# FootVibrator.net
KiCad netlist of a schematic drawn in EAGLE
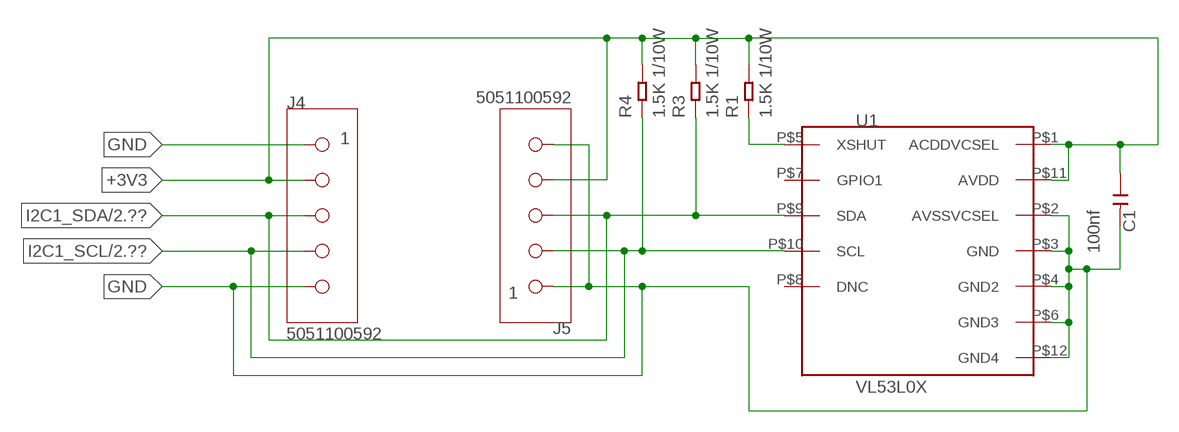
[diagram p0: schematic, sheet 1]
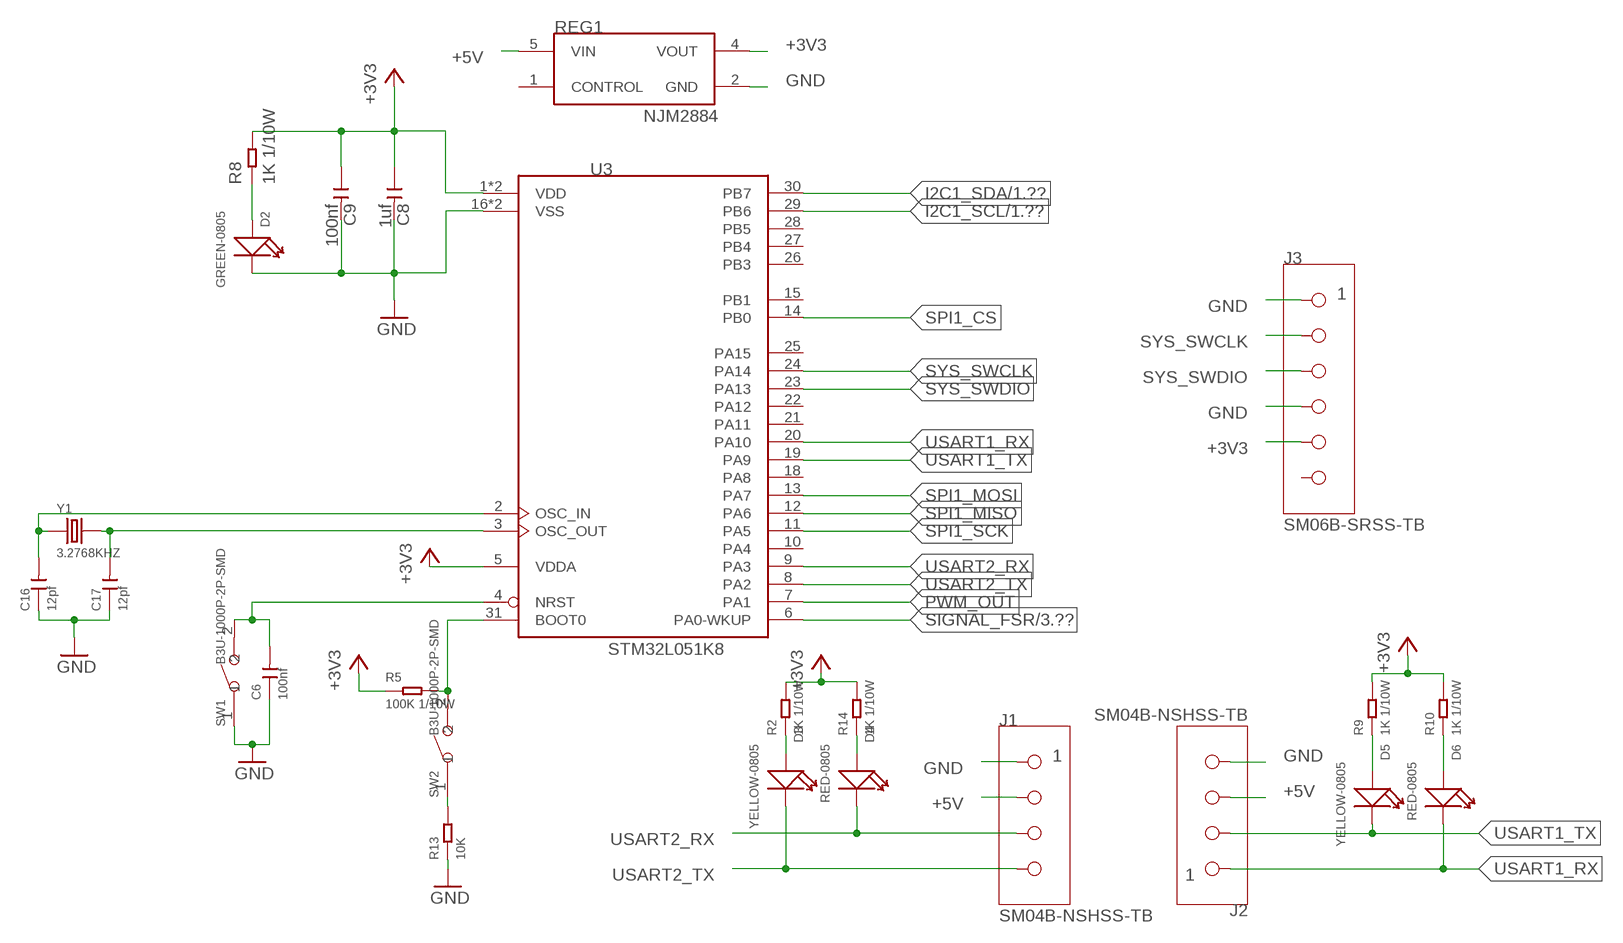
[diagram p1: schematic, sheet 2]
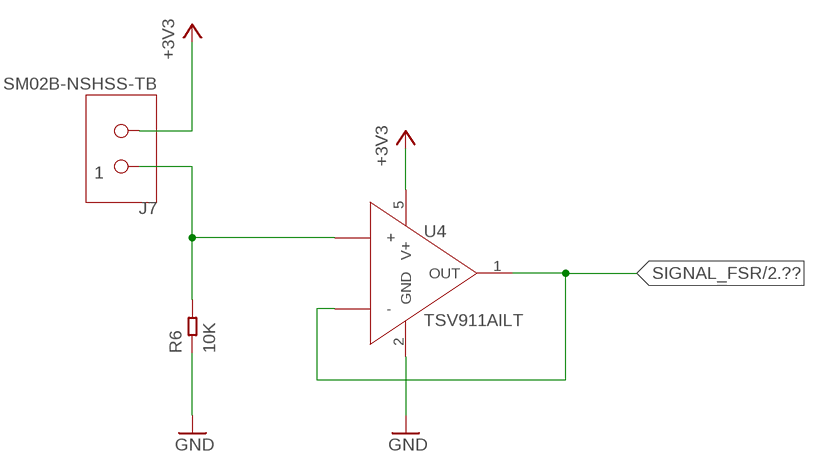
[diagram p2: schematic, sheet 3]
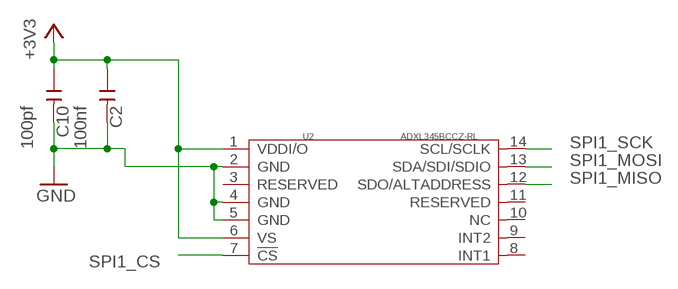
[diagram p3: schematic, sheet 4]
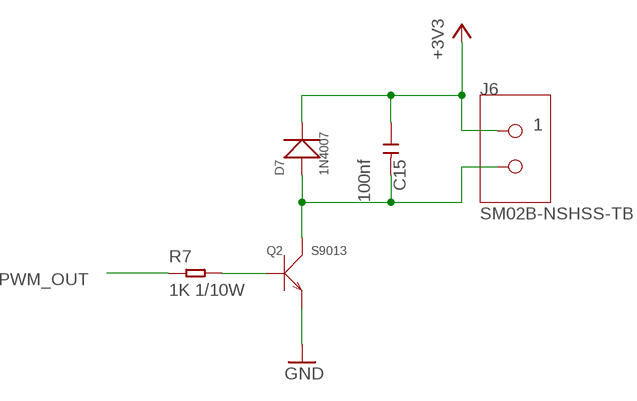
[diagram p4: schematic, sheet 5]

(export (version "E")
  (design (tool "Eeschema 10.0.6"))
  (components
    (comp (ref "C6")
      (value "100nf")
      (footprint "eagle-import:C0603")
      (fields (field (name "MPN") "CC0603KRX7R9BB104"))
      (libsource (lib "eagle-import") (part "CERAMIC-100NF-50V-10%-X7R(0603)"))
    )
    (comp (ref "C8")
      (value "1uf")
      (footprint "eagle-import:C0603")
      (fields (field (name "MPN") "CC0603KRX7R8BB105"))
      (libsource (lib "eagle-import") (part "CERAMIC-1UF-25V-10%-X7R(0603)"))
    )
    (comp (ref "C9")
      (value "100nf")
      (footprint "eagle-import:C0603")
      (fields (field (name "MPN") "CC0603KRX7R9BB104"))
      (libsource (lib "eagle-import") (part "CERAMIC-100NF-50V-10%-X7R(0603)"))
    )
    (comp (ref "C16")
      (value "12pf")
      (footprint "eagle-import:C0603")
      (fields (field (name "MPN") "CC0603JRNPO9BN120"))
      (libsource (lib "eagle-import") (part "CERAMIC-12PF-50V-5%-NPO(0603)"))
    )
    (comp (ref "C17")
      (value "12pf")
      (footprint "eagle-import:C0603")
      (fields (field (name "MPN") "CC0603JRNPO9BN120"))
      (libsource (lib "eagle-import") (part "CERAMIC-12PF-50V-5%-NPO(0603)"))
    )
    (comp (ref "D2")
      (value "GREEN-0805")
      (footprint "eagle-import:LED-0805")
      (fields (field (name "MPN") "17-215SYGC/S530-E2/TR8"))
      (libsource (lib "eagle-import") (part "SMD-LED-CLEAR-GREEN(0805)"))
    )
    (comp (ref "D3")
      (value "YELLOW-0805")
      (footprint "eagle-import:LED-0805")
      (fields (field (name "MPN") "17-215UYC/S530-A3/TR8"))
      (libsource (lib "eagle-import") (part "SMD-LED-CLEAR-YELLOW(0805)"))
    )
    (comp (ref "D4")
      (value "RED-0805")
      (footprint "eagle-import:LED-0805")
      (fields (field (name "MPN") "17-215SURC/S530-A2/TR8"))
      (libsource (lib "eagle-import") (part "SMD-LED-CLEAR-RED(0805)"))
    )
    (comp (ref "D5")
      (value "YELLOW-0805")
      (footprint "eagle-import:LED-0805")
      (fields (field (name "MPN") "17-215UYC/S530-A3/TR8"))
      (libsource (lib "eagle-import") (part "SMD-LED-CLEAR-YELLOW(0805)"))
    )
    (comp (ref "D6")
      (value "RED-0805")
      (footprint "eagle-import:LED-0805")
      (fields (field (name "MPN") "17-215SURC/S530-A2/TR8"))
      (libsource (lib "eagle-import") (part "SMD-LED-CLEAR-RED(0805)"))
    )
    (comp (ref "J1")
      (value "SM04B-NSHSS-TB")
      (footprint "eagle-import:SM04B-NSHSS-TB")
      (libsource (lib "eagle-import") (part "SM04B-NSHSS-TB"))
    )
    (comp (ref "J2")
      (value "SM04B-NSHSS-TB")
      (footprint "eagle-import:SM04B-NSHSS-TB")
      (libsource (lib "eagle-import") (part "SM04B-NSHSS-TB"))
    )
    (comp (ref "J3")
      (value "SM06B-SRSS-TB")
      (footprint "eagle-import:SM06B-SRSS-TB")
      (libsource (lib "eagle-import") (part "SM06B-SRSS-TB"))
    )
    (comp (ref "R2")
      (value "1K 1/10W")
      (footprint "eagle-import:R0603")
      (fields (field (name "MPN") "RC0603JR-071KL"))
      (libsource (lib "eagle-import") (part "SMD-RES-1K-5%-1/10W(0603)"))
    )
    (comp (ref "R5")
      (value "100K 1/10W")
      (footprint "eagle-import:R0603")
      (fields (field (name "MPN") "RC0603JR-07100KL"))
      (libsource (lib "eagle-import") (part "SMD-RES-100K-5%-1/10W(0603)"))
    )
    (comp (ref "R8")
      (value "1K 1/10W")
      (footprint "eagle-import:R0603")
      (fields (field (name "MPN") "RC0603JR-071KL"))
      (libsource (lib "eagle-import") (part "SMD-RES-1K-5%-1/10W(0603)"))
    )
    (comp (ref "R9")
      (value "1K 1/10W")
      (footprint "eagle-import:R0603")
      (fields (field (name "MPN") "RC0603JR-071KL"))
      (libsource (lib "eagle-import") (part "SMD-RES-1K-5%-1/10W(0603)"))
    )
    (comp (ref "R10")
      (value "1K 1/10W")
      (footprint "eagle-import:R0603")
      (fields (field (name "MPN") "RC0603JR-071KL"))
      (libsource (lib "eagle-import") (part "SMD-RES-1K-5%-1/10W(0603)"))
    )
    (comp (ref "R13")
      (value "10K")
      (footprint "eagle-import:R0603")
      (fields (field (name "MPN") "RC0603FR-0710KL"))
      (libsource (lib "eagle-import") (part "SMD-RES-10K-1%-1/10W(0603)"))
    )
    (comp (ref "R14")
      (value "1K 1/10W")
      (footprint "eagle-import:R0603")
      (fields (field (name "MPN") "RC0603JR-071KL"))
      (libsource (lib "eagle-import") (part "SMD-RES-1K-5%-1/10W(0603)"))
    )
    (comp (ref "REG1")
      (value "NJM2884")
      (footprint "eagle-import:NJM2884-SOT-89-5")
      (libsource (lib "eagle-import") (part "NJM2884"))
    )
    (comp (ref "SW1")
      (value "B3U-1000P-2P-SMD")
      (footprint "eagle-import:SW2-2.6-3.0X2.5X1.2+0.4MM")
      (libsource (lib "eagle-import") (part "SMD-BUTTON(2P-3.0X2.5X1.2+0.4MM)-B3U-1000P-2P-SMD"))
    )
    (comp (ref "SW2")
      (value "B3U-1000P-2P-SMD")
      (footprint "eagle-import:SW2-2.6-3.0X2.5X1.2+0.4MM")
      (libsource (lib "eagle-import") (part "SMD-BUTTON(2P-3.0X2.5X1.2+0.4MM)-B3U-1000P-2P-SMD"))
    )
    (comp (ref "U3")
      (value "STM32L051K8")
      (footprint "eagle-import:LQFP32")
      (libsource (lib "eagle-import") (part "STM32L051K8"))
    )
    (comp (ref "Y1")
      (value "3.2768KHZ")
      (footprint "eagle-import:X2-SMD-L2.0X1.2X0.55MM")
      (fields (field (name "MPN") "FC-12M"))
      (libsource (lib "eagle-import") (part "SMD-CRYSTAL-32.768KHZ-12.5PF-20PPM-90K(2P-L2.0X1.2MM)"))
    )
    (comp (ref "C15")
      (value "100nf")
      (footprint "eagle-import:C0603")
      (fields (field (name "MPN") "CC0603KRX7R9BB104"))
      (libsource (lib "eagle-import") (part "CERAMIC-100NF-50V-10%-X7R(0603)"))
    )
    (comp (ref "D7")
      (value "1N4007")
      (footprint "eagle-import:DO-214AC")
      (libsource (lib "eagle-import") (part "DIODE-GEN-PURPOSE-1KV-1A(DO-214AC)"))
    )
    (comp (ref "J6")
      (value "SM02B-NSHSS-TB")
      (footprint "eagle-import:SM02B-NSHSS-TB")
      (libsource (lib "eagle-import") (part "SM02B-NSHSS-TB"))
    )
    (comp (ref "Q2")
      (value "S9013")
      (footprint "eagle-import:SOT-23")
      (libsource (lib "eagle-import") (part "SMD-TRANSISTORS-NPN-25V-500MA-S9013(SOT-23)"))
    )
    (comp (ref "R7")
      (value "1K 1/10W")
      (footprint "eagle-import:R0603")
      (fields (field (name "MPN") "RC0603JR-071KL"))
      (libsource (lib "eagle-import") (part "SMD-RES-1K-5%-1/10W(0603)"))
    )
    (comp (ref "C1")
      (value "100nf")
      (footprint "eagle-import:C0603")
      (fields (field (name "MPN") "CC0603KRX7R9BB104"))
      (libsource (lib "eagle-import") (part "CERAMIC-100NF-50V-10%-X7R(0603)"))
    )
    (comp (ref "J4")
      (value "5051100592")
      (footprint "eagle-import:5051100592")
      (libsource (lib "eagle-import") (part "5051100592"))
    )
    (comp (ref "J5")
      (value "5051100592")
      (footprint "eagle-import:5051100592")
      (libsource (lib "eagle-import") (part "5051100592"))
    )
    (comp (ref "R1")
      (value "1.5K 1/10W")
      (footprint "eagle-import:R0603")
      (fields (field (name "MPN") "RC0603JR-071K5L"))
      (libsource (lib "eagle-import") (part "SMD-RES-1.5K-5%-1/10W(0603)"))
    )
    (comp (ref "R3")
      (value "1.5K 1/10W")
      (footprint "eagle-import:R0603")
      (fields (field (name "MPN") "RC0603JR-071K5L"))
      (libsource (lib "eagle-import") (part "SMD-RES-1.5K-5%-1/10W(0603)"))
    )
    (comp (ref "R4")
      (value "1.5K 1/10W")
      (footprint "eagle-import:R0603")
      (fields (field (name "MPN") "RC0603JR-071K5L"))
      (libsource (lib "eagle-import") (part "SMD-RES-1.5K-5%-1/10W(0603)"))
    )
    (comp (ref "U1")
      (value "VL53L0X")
      (footprint "eagle-import:VL53L0X")
      (libsource (lib "eagle-import") (part "VL53L0X"))
    )
    (comp (ref "J7")
      (value "SM02B-NSHSS-TB")
      (footprint "eagle-import:SM02B-NSHSS-TB")
      (libsource (lib "eagle-import") (part "SM02B-NSHSS-TB"))
    )
    (comp (ref "R6")
      (value "10K")
      (footprint "eagle-import:R0603")
      (fields (field (name "MPN") "RC0603FR-0710KL"))
      (libsource (lib "eagle-import") (part "SMD-RES-10K-1%-1/10W(0603)"))
    )
    (comp (ref "U4")
      (value "TSV911AILT")
      (footprint "eagle-import:SOT23-5")
      (libsource (lib "eagle-import") (part "TSV911AILT"))
    )
    (comp (ref "C2")
      (value "100nf")
      (footprint "eagle-import:C0603")
      (fields (field (name "MPN") "CC0603KRX7R9BB104"))
      (libsource (lib "eagle-import") (part "CERAMIC-100NF-50V-10%-X7R(0603)"))
    )
    (comp (ref "C10")
      (value "100pf")
      (footprint "eagle-import:C0603")
      (fields (field (name "MPN") "CC0603JRNPO9BN101"))
      (libsource (lib "eagle-import") (part "CERAMIC-100PF-50V-5%-NPO(0603)"))
    )
    (comp (ref "U2")
      (value "ADXL345BCCZ-RL")
      (footprint "eagle-import:LGA14-0.8-5.0X3.0MM")
      (libsource (lib "eagle-import") (part "MOTION/POSITION-ADXL345BCCZ-RL(14P-5.0X3.0MM)"))
    )
  )
  (nets
    (net (code "1") (name "+3V3") (class "Default")
      (node (ref "C1") (pin "1") (pinfunction "1_1") (pintype "passive"))
      (node (ref "C10") (pin "1") (pinfunction "1_1") (pintype "passive"))
      (node (ref "C15") (pin "1") (pinfunction "1_1") (pintype "passive"))
      (node (ref "C2") (pin "1") (pinfunction "1_1") (pintype "passive"))
      (node (ref "C8") (pin "1") (pinfunction "1_1") (pintype "passive"))
      (node (ref "C9") (pin "1") (pinfunction "1_1") (pintype "passive"))
      (node (ref "D7") (pin "2") (pinfunction "-_2") (pintype "passive"))
      (node (ref "J3") (pin "5") (pinfunction "5_5") (pintype "bidirectional"))
      (node (ref "J4") (pin "2") (pinfunction "2_2") (pintype "bidirectional"))
      (node (ref "J5") (pin "4") (pinfunction "4_4") (pintype "bidirectional"))
      (node (ref "J6") (pin "P$1") (pinfunction "1_P$1") (pintype "bidirectional"))
      (node (ref "J7") (pin "P$2") (pinfunction "2_P$2") (pintype "bidirectional"))
      (node (ref "R1") (pin "2") (pinfunction "2_2") (pintype "passive"))
      (node (ref "R10") (pin "2") (pinfunction "2_2") (pintype "passive"))
      (node (ref "R14") (pin "2") (pinfunction "2_2") (pintype "passive"))
      (node (ref "R2") (pin "2") (pinfunction "2_2") (pintype "passive"))
      (node (ref "R3") (pin "2") (pinfunction "2_2") (pintype "passive"))
      (node (ref "R4") (pin "2") (pinfunction "2_2") (pintype "passive"))
      (node (ref "R5") (pin "1") (pinfunction "1_1") (pintype "passive"))
      (node (ref "R8") (pin "2") (pinfunction "2_2") (pintype "passive"))
      (node (ref "R9") (pin "2") (pinfunction "2_2") (pintype "passive"))
      (node (ref "REG1") (pin "4") (pinfunction "VOUT_4") (pintype "power_in"))
      (node (ref "U1") (pin "P$1") (pinfunction "ACDDVCSEL_P$1") (pintype "bidirectional"))
      (node (ref "U1") (pin "P$11") (pinfunction "AVDD_P$11") (pintype "bidirectional"))
      (node (ref "U2") (pin "1") (pinfunction "VDDI/O_1") (pintype "power_in"))
      (node (ref "U2") (pin "6") (pinfunction "VS_6") (pintype "bidirectional"))
      (node (ref "U3") (pin "1") (pinfunction "VDD_1") (pintype "bidirectional"))
      (node (ref "U3") (pin "17") (pinfunction "VDD_17") (pintype "bidirectional"))
      (node (ref "U3") (pin "5") (pinfunction "VDDA_5") (pintype "power_in"))
      (node (ref "U4") (pin "5") (pinfunction "V+_5") (pintype "bidirectional"))
    )
    (net (code "2") (name "+5V") (class "Default")
      (node (ref "J1") (pin "P$2") (pinfunction "2_P$2") (pintype "bidirectional"))
      (node (ref "J2") (pin "P$3") (pinfunction "3_P$3") (pintype "bidirectional"))
      (node (ref "REG1") (pin "5") (pinfunction "VIN_5") (pintype "power_in"))
    )
    (net (code "3") (name "GND") (class "Default")
      (node (ref "C1") (pin "2") (pinfunction "2_2") (pintype "passive"))
      (node (ref "C10") (pin "2") (pinfunction "2_2") (pintype "passive"))
      (node (ref "C16") (pin "1") (pinfunction "1_1") (pintype "passive"))
      (node (ref "C17") (pin "1") (pinfunction "1_1") (pintype "passive"))
      (node (ref "C2") (pin "2") (pinfunction "2_2") (pintype "passive"))
      (node (ref "C6") (pin "1") (pinfunction "1_1") (pintype "passive"))
      (node (ref "C8") (pin "2") (pinfunction "2_2") (pintype "passive"))
      (node (ref "C9") (pin "2") (pinfunction "2_2") (pintype "passive"))
      (node (ref "D2") (pin "-") (pinfunction "-_-") (pintype "passive"))
      (node (ref "J1") (pin "P$1") (pinfunction "1_P$1") (pintype "bidirectional"))
      (node (ref "J2") (pin "P$4") (pinfunction "4_P$4") (pintype "bidirectional"))
      (node (ref "J3") (pin "1") (pinfunction "1_1") (pintype "bidirectional"))
      (node (ref "J3") (pin "4") (pinfunction "4_4") (pintype "bidirectional"))
      (node (ref "J4") (pin "1") (pinfunction "1_1") (pintype "bidirectional"))
      (node (ref "J4") (pin "5") (pinfunction "5_5") (pintype "bidirectional"))
      (node (ref "J5") (pin "1") (pinfunction "1_1") (pintype "bidirectional"))
      (node (ref "J5") (pin "5") (pinfunction "5_5") (pintype "bidirectional"))
      (node (ref "Q2") (pin "2") (pinfunction "E_2") (pintype "passive"))
      (node (ref "R13") (pin "1") (pinfunction "1_1") (pintype "passive"))
      (node (ref "R6") (pin "1") (pinfunction "1_1") (pintype "passive"))
      (node (ref "REG1") (pin "2") (pinfunction "GND_2") (pintype "power_in"))
      (node (ref "SW1") (pin "1") (pinfunction "1_1") (pintype "bidirectional"))
      (node (ref "U1") (pin "P$12") (pinfunction "GND4_P$12") (pintype "bidirectional"))
      (node (ref "U1") (pin "P$2") (pinfunction "AVSSVCSEL_P$2") (pintype "bidirectional"))
      (node (ref "U1") (pin "P$3") (pinfunction "GND_P$3") (pintype "bidirectional"))
      (node (ref "U1") (pin "P$4") (pinfunction "GND2_P$4") (pintype "bidirectional"))
      (node (ref "U1") (pin "P$6") (pinfunction "GND3_P$6") (pintype "bidirectional"))
      (node (ref "U2") (pin "2") (pinfunction "GND_2") (pintype "power_in"))
      (node (ref "U2") (pin "4") (pinfunction "GND_4") (pintype "power_in"))
      (node (ref "U2") (pin "5") (pinfunction "GND_5") (pintype "power_in"))
      (node (ref "U3") (pin "16") (pinfunction "VSS_16") (pintype "bidirectional"))
      (node (ref "U3") (pin "32") (pinfunction "VSS_32") (pintype "bidirectional"))
      (node (ref "U4") (pin "2") (pinfunction "GND_2") (pintype "bidirectional"))
    )
    (net (code "4") (name "I2C1_SCL") (class "Default")
      (node (ref "J4") (pin "4") (pinfunction "4_4") (pintype "bidirectional"))
      (node (ref "J5") (pin "2") (pinfunction "2_2") (pintype "bidirectional"))
      (node (ref "R4") (pin "1") (pinfunction "1_1") (pintype "passive"))
      (node (ref "U1") (pin "P$10") (pinfunction "SCL_P$10") (pintype "bidirectional"))
      (node (ref "U3") (pin "29") (pinfunction "PB6_29") (pintype "bidirectional"))
    )
    (net (code "5") (name "I2C1_SDA") (class "Default")
      (node (ref "J4") (pin "3") (pinfunction "3_3") (pintype "bidirectional"))
      (node (ref "J5") (pin "3") (pinfunction "3_3") (pintype "bidirectional"))
      (node (ref "R3") (pin "1") (pinfunction "1_1") (pintype "passive"))
      (node (ref "U1") (pin "P$9") (pinfunction "SDA_P$9") (pintype "bidirectional"))
      (node (ref "U3") (pin "30") (pinfunction "PB7_30") (pintype "bidirectional"))
    )
    (net (code "6") (name "Net-(D2-Pad+)") (class "Default")
      (node (ref "D2") (pin "+") (pinfunction "+_+") (pintype "passive"))
      (node (ref "R8") (pin "1") (pinfunction "1_1") (pintype "passive"))
    )
    (net (code "7") (name "Net-(D3-Pad+)") (class "Default")
      (node (ref "D3") (pin "+") (pinfunction "+_+") (pintype "passive"))
      (node (ref "R2") (pin "1") (pinfunction "1_1") (pintype "passive"))
    )
    (net (code "8") (name "Net-(D4-Pad+)") (class "Default")
      (node (ref "D4") (pin "+") (pinfunction "+_+") (pintype "passive"))
      (node (ref "R14") (pin "1") (pinfunction "1_1") (pintype "passive"))
    )
    (net (code "9") (name "Net-(D5-Pad+)") (class "Default")
      (node (ref "D5") (pin "+") (pinfunction "+_+") (pintype "passive"))
      (node (ref "R9") (pin "1") (pinfunction "1_1") (pintype "passive"))
    )
    (net (code "10") (name "Net-(D6-Pad+)") (class "Default")
      (node (ref "D6") (pin "+") (pinfunction "+_+") (pintype "passive"))
      (node (ref "R10") (pin "1") (pinfunction "1_1") (pintype "passive"))
    )
    (net (code "11") (name "Net-(D7-+)") (class "Default")
      (node (ref "C15") (pin "2") (pinfunction "2_2") (pintype "passive"))
      (node (ref "D7") (pin "1") (pinfunction "+_1") (pintype "passive"))
      (node (ref "J6") (pin "P$2") (pinfunction "2_P$2") (pintype "bidirectional"))
      (node (ref "Q2") (pin "3") (pinfunction "C_3") (pintype "passive"))
    )
    (net (code "12") (name "Net-(J7-1)") (class "Default")
      (node (ref "J7") (pin "P$1") (pinfunction "1_P$1") (pintype "bidirectional"))
      (node (ref "R6") (pin "2") (pinfunction "2_2") (pintype "passive"))
      (node (ref "U4") (pin "3") (pinfunction "+_3") (pintype "bidirectional"))
    )
    (net (code "13") (name "Net-(Q2-B)") (class "Default")
      (node (ref "Q2") (pin "1") (pinfunction "B_1") (pintype "passive"))
      (node (ref "R7") (pin "2") (pinfunction "2_2") (pintype "passive"))
    )
    (net (code "14") (name "Net-(R13-Pad2)") (class "Default")
      (node (ref "R13") (pin "2") (pinfunction "2_2") (pintype "passive"))
      (node (ref "SW2") (pin "1") (pinfunction "1_1") (pintype "bidirectional"))
    )
    (net (code "15") (name "Net-(U1-XSHUT)") (class "Default")
      (node (ref "R1") (pin "1") (pinfunction "1_1") (pintype "passive"))
      (node (ref "U1") (pin "P$5") (pinfunction "XSHUT_P$5") (pintype "bidirectional"))
    )
    (net (code "16") (name "Net-(U3-BOOT0)") (class "Default")
      (node (ref "R5") (pin "2") (pinfunction "2_2") (pintype "passive"))
      (node (ref "SW2") (pin "2") (pinfunction "2_2") (pintype "bidirectional"))
      (node (ref "U3") (pin "31") (pinfunction "BOOT0_31") (pintype "input"))
    )
    (net (code "17") (name "Net-(U3-NRST)") (class "Default")
      (node (ref "C6") (pin "2") (pinfunction "2_2") (pintype "passive"))
      (node (ref "SW1") (pin "2") (pinfunction "2_2") (pintype "bidirectional"))
      (node (ref "U3") (pin "4") (pinfunction "NRST_4") (pintype "bidirectional"))
    )
    (net (code "18") (name "Net-(U3-OSC_IN)") (class "Default")
      (node (ref "C16") (pin "2") (pinfunction "2_2") (pintype "passive"))
      (node (ref "U3") (pin "2") (pinfunction "OSC_IN_2") (pintype "bidirectional"))
      (node (ref "Y1") (pin "1") (pinfunction "1_1") (pintype "passive"))
    )
    (net (code "19") (name "Net-(U3-OSC_OUT)") (class "Default")
      (node (ref "C17") (pin "2") (pinfunction "2_2") (pintype "passive"))
      (node (ref "U3") (pin "3") (pinfunction "OSC_OUT_3") (pintype "bidirectional"))
      (node (ref "Y1") (pin "2") (pinfunction "2_2") (pintype "passive"))
    )
    (net (code "20") (name "PWM_OUT") (class "Default")
      (node (ref "R7") (pin "1") (pinfunction "1_1") (pintype "passive"))
      (node (ref "U3") (pin "7") (pinfunction "PA1_7") (pintype "bidirectional"))
    )
    (net (code "21") (name "SIGNAL_FSR") (class "Default")
      (node (ref "U3") (pin "6") (pinfunction "PA0-WKUP_6") (pintype "bidirectional"))
      (node (ref "U4") (pin "1") (pinfunction "OUT_1") (pintype "bidirectional"))
      (node (ref "U4") (pin "4") (pinfunction "-_4") (pintype "bidirectional"))
    )
    (net (code "22") (name "SPI1_CS") (class "Default")
      (node (ref "U2") (pin "7") (pinfunction "~{CS}_7") (pintype "bidirectional"))
      (node (ref "U3") (pin "14") (pinfunction "PB0_14") (pintype "bidirectional"))
    )
    (net (code "23") (name "SPI1_MISO") (class "Default")
      (node (ref "U2") (pin "12") (pinfunction "SDO/ALTADDRESS_12") (pintype "bidirectional"))
      (node (ref "U3") (pin "12") (pinfunction "PA6_12") (pintype "bidirectional"))
    )
    (net (code "24") (name "SPI1_MOSI") (class "Default")
      (node (ref "U2") (pin "13") (pinfunction "SDA/SDI/SDIO_13") (pintype "bidirectional"))
      (node (ref "U3") (pin "13") (pinfunction "PA7_13") (pintype "bidirectional"))
    )
    (net (code "25") (name "SPI1_SCK") (class "Default")
      (node (ref "U2") (pin "14") (pinfunction "SCL/SCLK_14") (pintype "input"))
      (node (ref "U3") (pin "11") (pinfunction "PA5_11") (pintype "bidirectional"))
    )
    (net (code "26") (name "SYS_SWCLK") (class "Default")
      (node (ref "J3") (pin "2") (pinfunction "2_2") (pintype "bidirectional"))
      (node (ref "U3") (pin "24") (pinfunction "PA14_24") (pintype "bidirectional"))
    )
    (net (code "27") (name "SYS_SWDIO") (class "Default")
      (node (ref "J3") (pin "3") (pinfunction "3_3") (pintype "bidirectional"))
      (node (ref "U3") (pin "23") (pinfunction "PA13_23") (pintype "bidirectional"))
    )
    (net (code "28") (name "USART1_RX") (class "Default")
      (node (ref "D6") (pin "-") (pinfunction "-_-") (pintype "passive"))
      (node (ref "J2") (pin "P$1") (pinfunction "1_P$1") (pintype "bidirectional"))
      (node (ref "U3") (pin "20") (pinfunction "PA10_20") (pintype "bidirectional"))
    )
    (net (code "29") (name "USART1_TX") (class "Default")
      (node (ref "D5") (pin "-") (pinfunction "-_-") (pintype "passive"))
      (node (ref "J2") (pin "P$2") (pinfunction "2_P$2") (pintype "bidirectional"))
      (node (ref "U3") (pin "19") (pinfunction "PA9_19") (pintype "bidirectional"))
    )
    (net (code "30") (name "USART2_RX") (class "Default")
      (node (ref "D4") (pin "-") (pinfunction "-_-") (pintype "passive"))
      (node (ref "J1") (pin "P$3") (pinfunction "3_P$3") (pintype "bidirectional"))
      (node (ref "U3") (pin "9") (pinfunction "PA3_9") (pintype "bidirectional"))
    )
    (net (code "31") (name "USART2_TX") (class "Default")
      (node (ref "D3") (pin "-") (pinfunction "-_-") (pintype "passive"))
      (node (ref "J1") (pin "P$4") (pinfunction "4_P$4") (pintype "bidirectional"))
      (node (ref "U3") (pin "8") (pinfunction "PA2_8") (pintype "bidirectional"))
    )
    (net (code "32") (name "unconnected-(J3-Pad6)") (class "Default")
      (node (ref "J3") (pin "6") (pinfunction "6_6") (pintype "bidirectional"))
    )
    (net (code "33") (name "unconnected-(REG1-CONTROL-Pad1)") (class "Default")
      (node (ref "REG1") (pin "1") (pinfunction "CONTROL_1") (pintype "bidirectional"))
    )
    (net (code "34") (name "unconnected-(U1-DNC-PadP$8)") (class "Default")
      (node (ref "U1") (pin "P$8") (pinfunction "DNC_P$8") (pintype "bidirectional"))
    )
    (net (code "35") (name "unconnected-(U1-GPIO1-PadP$7)") (class "Default")
      (node (ref "U1") (pin "P$7") (pinfunction "GPIO1_P$7") (pintype "bidirectional"))
    )
    (net (code "36") (name "unconnected-(U2-INT1-Pad8)") (class "Default")
      (node (ref "U2") (pin "8") (pinfunction "INT1_8") (pintype "bidirectional"))
    )
    (net (code "37") (name "unconnected-(U2-INT2-Pad9)") (class "Default")
      (node (ref "U2") (pin "9") (pinfunction "INT2_9") (pintype "bidirectional"))
    )
    (net (code "38") (name "unconnected-(U2-NC-Pad10)") (class "Default")
      (node (ref "U2") (pin "10") (pinfunction "NC_10") (pintype "no_connect"))
    )
    (net (code "39") (name "unconnected-(U2-RESERVED-Pad3)") (class "Default")
      (node (ref "U2") (pin "3") (pinfunction "RESERVED_3") (pintype "bidirectional"))
    )
    (net (code "40") (name "unconnected-(U2-RESERVED-Pad11)") (class "Default")
      (node (ref "U2") (pin "11") (pinfunction "RESERVED_11") (pintype "bidirectional"))
    )
    (net (code "41") (name "unconnected-(U3-PA4-Pad10)") (class "Default")
      (node (ref "U3") (pin "10") (pinfunction "PA4_10") (pintype "bidirectional"))
    )
    (net (code "42") (name "unconnected-(U3-PA8-Pad18)") (class "Default")
      (node (ref "U3") (pin "18") (pinfunction "PA8_18") (pintype "bidirectional"))
    )
    (net (code "43") (name "unconnected-(U3-PA11-Pad21)") (class "Default")
      (node (ref "U3") (pin "21") (pinfunction "PA11_21") (pintype "bidirectional"))
    )
    (net (code "44") (name "unconnected-(U3-PA12-Pad22)") (class "Default")
      (node (ref "U3") (pin "22") (pinfunction "PA12_22") (pintype "bidirectional"))
    )
    (net (code "45") (name "unconnected-(U3-PA15-Pad25)") (class "Default")
      (node (ref "U3") (pin "25") (pinfunction "PA15_25") (pintype "bidirectional"))
    )
    (net (code "46") (name "unconnected-(U3-PB1-Pad15)") (class "Default")
      (node (ref "U3") (pin "15") (pinfunction "PB1_15") (pintype "bidirectional"))
    )
    (net (code "47") (name "unconnected-(U3-PB3-Pad26)") (class "Default")
      (node (ref "U3") (pin "26") (pinfunction "PB3_26") (pintype "bidirectional"))
    )
    (net (code "48") (name "unconnected-(U3-PB4-Pad27)") (class "Default")
      (node (ref "U3") (pin "27") (pinfunction "PB4_27") (pintype "bidirectional"))
    )
    (net (code "49") (name "unconnected-(U3-PB5-Pad28)") (class "Default")
      (node (ref "U3") (pin "28") (pinfunction "PB5_28") (pintype "bidirectional"))
    )
  )
)
